# TPS63001DRCR_Buck_Boost_Converter.net
KiCad netlist of a schematic drawn in EAGLE
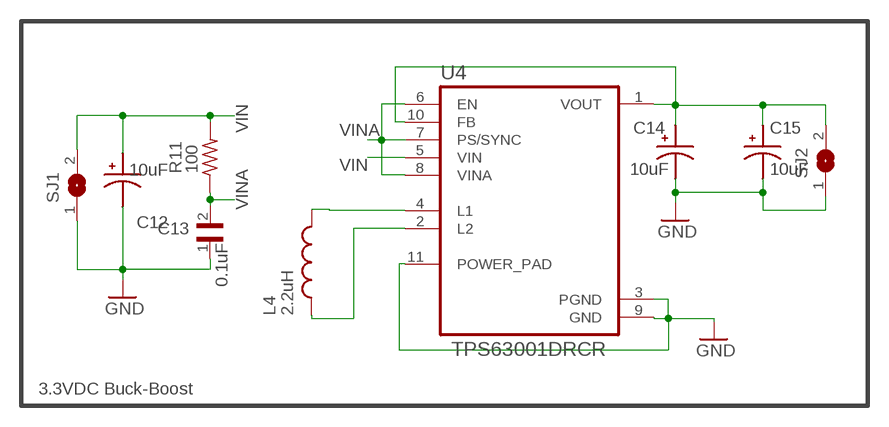
[diagram p0: schematic, sheet 1]

(export (version "E")
  (design (tool "Eeschema 10.0.6"))
  (components
    (comp (ref "C12")
      (value "10uF")
      (footprint "eagle-import:CAPAE430X550N")
      (fields (field (name "MF") "Panasonic") (field (name "MP") "EEE-1CA100SR"))
      (libsource (lib "eagle-import") (part "EEE-1CA100SR"))
    )
    (comp (ref "C13")
      (value "0.1uF")
      (footprint "eagle-import:CAPC1608X100N")
      (fields (field (name "MF") "Murata") (field (name "MP") "GRM188C81C106MA73J"))
      (libsource (lib "eagle-import") (part "GRM188C81C106MA73J"))
    )
    (comp (ref "C14")
      (value "10uF")
      (footprint "eagle-import:CAPAE430X550N")
      (fields (field (name "MF") "Panasonic") (field (name "MP") "EEE-1CA100SR"))
      (libsource (lib "eagle-import") (part "EEE-1CA100SR"))
    )
    (comp (ref "C15")
      (value "10uF")
      (footprint "eagle-import:CAPAE430X550N")
      (fields (field (name "MF") "Panasonic") (field (name "MP") "EEE-1CA100SR"))
      (libsource (lib "eagle-import") (part "EEE-1CA100SR"))
    )
    (comp (ref "L4")
      (value "2.2uH")
      (footprint "eagle-import:INDC1608X95N")
      (fields (field (name "MF") "Murata") (field (name "MP") "LQM18PN2R2MFHD"))
      (libsource (lib "eagle-import") (part "LQM18PN2R2MFHD"))
    )
    (comp (ref "R11")
      (value "100")
      (footprint "eagle-import:RESC2012X65N")
      (fields (field (name "MF") "TE Connectivity") (field (name "MP") "RP73PF2A10KBTDF"))
      (libsource (lib "eagle-import") (part "RP73PF2A10KBTDF"))
    )
    (comp (ref "SJ1")
      (value "SJW")
      (footprint "eagle-import:SJW")
      (libsource (lib "eagle-import") (part "SJW"))
    )
    (comp (ref "SJ2")
      (value "SJW")
      (footprint "eagle-import:SJW")
      (libsource (lib "eagle-import") (part "SJW"))
    )
    (comp (ref "U4")
      (value "TPS63001DRCR")
      (footprint "eagle-import:VREG_V62_16624-01YE")
      (fields (field (name "MF") "Texas Instruments"))
      (libsource (lib "eagle-import") (part "TPS63001DRCR"))
    )
  )
  (nets
    (net (code "1") (name "/VIN") (class "Default")
      (node (ref "C12") (pin "1") (pinfunction "1_1") (pintype "passive"))
      (node (ref "R11") (pin "2") (pinfunction "2_2") (pintype "passive"))
      (node (ref "SJ1") (pin "2") (pinfunction "2_2") (pintype "passive"))
      (node (ref "U4") (pin "5") (pinfunction "VIN_5") (pintype "input"))
    )
    (net (code "2") (name "/VINA") (class "Default")
      (node (ref "C13") (pin "2") (pinfunction "2_2") (pintype "passive"))
      (node (ref "R11") (pin "1") (pinfunction "1_1") (pintype "passive"))
      (node (ref "U4") (pin "6") (pinfunction "EN_6") (pintype "input"))
      (node (ref "U4") (pin "7") (pinfunction "PS/SYNC_7") (pintype "input"))
      (node (ref "U4") (pin "8") (pinfunction "VINA_8") (pintype "input"))
    )
    (net (code "3") (name "GND") (class "Default")
      (node (ref "C12") (pin "2") (pinfunction "2_2") (pintype "passive"))
      (node (ref "C13") (pin "1") (pinfunction "1_1") (pintype "passive"))
      (node (ref "C14") (pin "2") (pinfunction "2_2") (pintype "passive"))
      (node (ref "C15") (pin "2") (pinfunction "2_2") (pintype "passive"))
      (node (ref "SJ1") (pin "1") (pinfunction "1_1") (pintype "passive"))
      (node (ref "SJ2") (pin "1") (pinfunction "1_1") (pintype "passive"))
      (node (ref "U4") (pin "11") (pinfunction "POWER_PAD_11") (pintype "bidirectional"))
      (node (ref "U4") (pin "3") (pinfunction "PGND_3") (pintype "power_in"))
      (node (ref "U4") (pin "9") (pinfunction "GND_9") (pintype "power_in"))
    )
    (net (code "4") (name "Net-(U4-FB)") (class "Default")
      (node (ref "C14") (pin "1") (pinfunction "1_1") (pintype "passive"))
      (node (ref "C15") (pin "1") (pinfunction "1_1") (pintype "passive"))
      (node (ref "SJ2") (pin "2") (pinfunction "2_2") (pintype "passive"))
      (node (ref "U4") (pin "1") (pinfunction "VOUT_1") (pintype "output"))
      (node (ref "U4") (pin "10") (pinfunction "FB_10") (pintype "input"))
    )
    (net (code "5") (name "Net-(U4-L1)") (class "Default")
      (node (ref "L4") (pin "2") (pinfunction "2_2") (pintype "passive"))
      (node (ref "U4") (pin "4") (pinfunction "L1_4") (pintype "bidirectional"))
    )
    (net (code "6") (name "Net-(U4-L2)") (class "Default")
      (node (ref "L4") (pin "1") (pinfunction "1_1") (pintype "passive"))
      (node (ref "U4") (pin "2") (pinfunction "L2_2") (pintype "bidirectional"))
    )
  )
)
